# N33_1_0.net
KiCad netlist of a schematic drawn in EAGLE
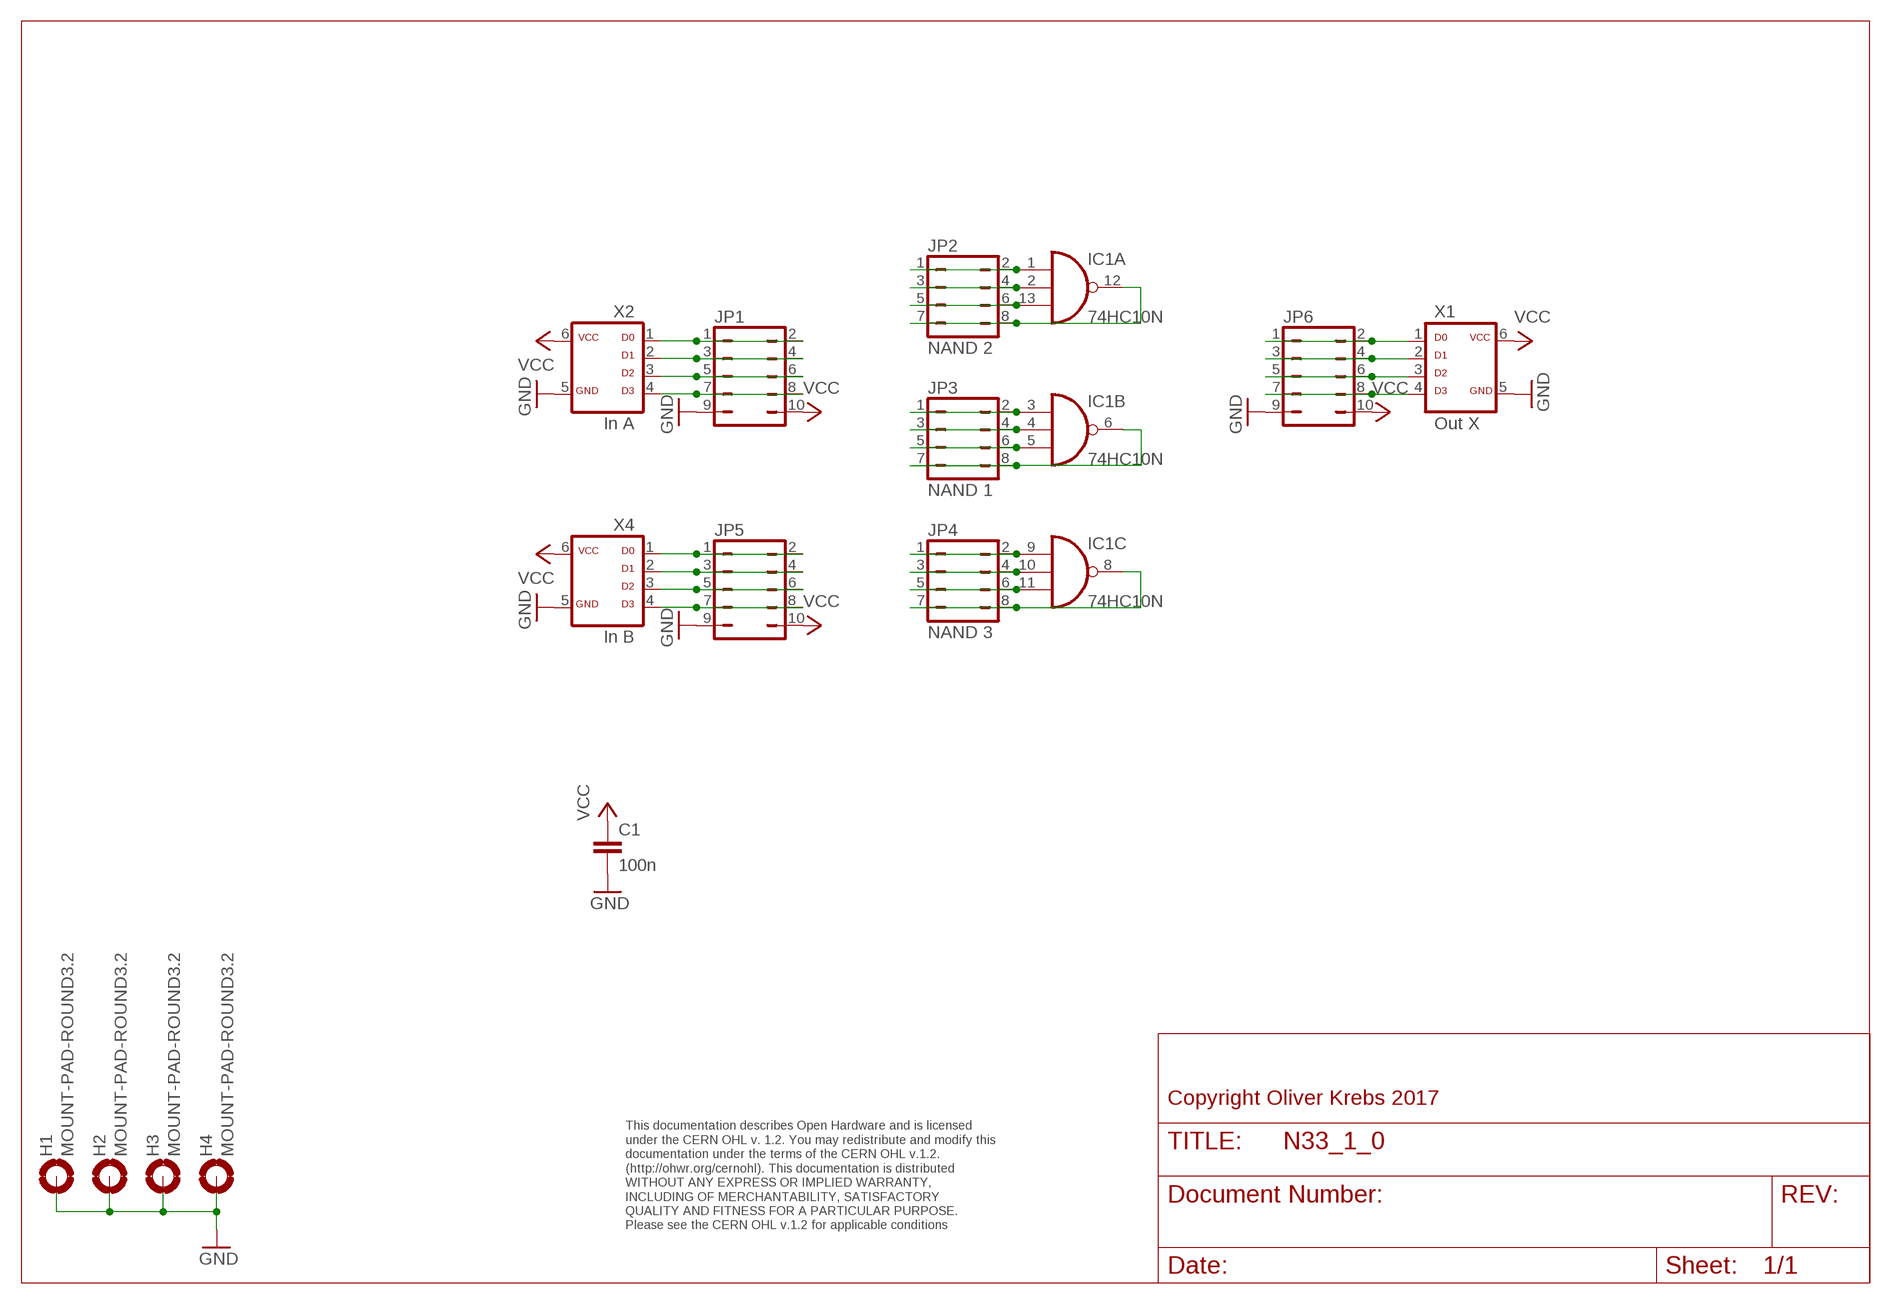
[diagram p0: schematic, sheet 1]

(export (version "E")
  (design (tool "Eeschema 10.0.6"))
  (components
    (comp (ref "C1")
      (value "100n")
      (footprint "eagle-import:C050-025X075")
      (libsource (lib "eagle-import") (part "C-EU050-025X075"))
    )
    (comp (ref "H1")
      (value "MOUNT-PAD-ROUND3.2")
      (footprint "eagle-import:3,2-PAD")
      (libsource (lib "eagle-import") (part "MOUNT-PAD-ROUND3.2"))
    )
    (comp (ref "H2")
      (value "MOUNT-PAD-ROUND3.2")
      (footprint "eagle-import:3,2-PAD")
      (libsource (lib "eagle-import") (part "MOUNT-PAD-ROUND3.2"))
    )
    (comp (ref "H3")
      (value "MOUNT-PAD-ROUND3.2")
      (footprint "eagle-import:3,2-PAD")
      (libsource (lib "eagle-import") (part "MOUNT-PAD-ROUND3.2"))
    )
    (comp (ref "H4")
      (value "MOUNT-PAD-ROUND3.2")
      (footprint "eagle-import:3,2-PAD")
      (libsource (lib "eagle-import") (part "MOUNT-PAD-ROUND3.2"))
    )
    (comp (ref "IC1")
      (value "74HC10N")
      (footprint "eagle-import:DIL14")
      (libsource (lib "eagle-import") (part "7410NHC"))
    )
    (comp (ref "JP1")
      (value "JP5Q")
      (footprint "eagle-import:JP5Q")
      (libsource (lib "eagle-import") (part "JP5Q"))
    )
    (comp (ref "JP2")
      (value "NAND 2")
      (footprint "eagle-import:JP4Q")
      (libsource (lib "eagle-import") (part "JP4Q"))
    )
    (comp (ref "JP3")
      (value "NAND 1")
      (footprint "eagle-import:JP4Q")
      (libsource (lib "eagle-import") (part "JP4Q"))
    )
    (comp (ref "JP4")
      (value "NAND 3")
      (footprint "eagle-import:JP4Q")
      (libsource (lib "eagle-import") (part "JP4Q"))
    )
    (comp (ref "JP5")
      (value "JP5Q")
      (footprint "eagle-import:JP5Q")
      (libsource (lib "eagle-import") (part "JP5Q"))
    )
    (comp (ref "JP6")
      (value "JP5Q")
      (footprint "eagle-import:JP5Q")
      (libsource (lib "eagle-import") (part "JP5Q"))
    )
    (comp (ref "X1")
      (value "Out X")
      (footprint "eagle-import:ML-6")
      (libsource (lib "eagle-import") (part "ML6D"))
    )
    (comp (ref "X2")
      (value "In A")
      (footprint "eagle-import:ML-6")
      (libsource (lib "eagle-import") (part "ML6D"))
    )
    (comp (ref "X4")
      (value "In B")
      (footprint "eagle-import:ML-6")
      (libsource (lib "eagle-import") (part "ML6D"))
    )
  )
  (nets
    (net (code "1") (name "GND") (class "Default")
      (node (ref "C1") (pin "2") (pinfunction "2_2") (pintype "passive"))
      (node (ref "H1") (pin "B3,2") (pinfunction "MOUNT_B3,2") (pintype "passive"))
      (node (ref "H2") (pin "B3,2") (pinfunction "MOUNT_B3,2") (pintype "passive"))
      (node (ref "H3") (pin "B3,2") (pinfunction "MOUNT_B3,2") (pintype "passive"))
      (node (ref "H4") (pin "B3,2") (pinfunction "MOUNT_B3,2") (pintype "passive"))
      (node (ref "JP1") (pin "9") (pinfunction "9_9") (pintype "passive"))
      (node (ref "JP5") (pin "9") (pinfunction "9_9") (pintype "passive"))
      (node (ref "JP6") (pin "9") (pinfunction "9_9") (pintype "passive"))
      (node (ref "X1") (pin "5") (pinfunction "5_5") (pintype "passive"))
      (node (ref "X2") (pin "5") (pinfunction "5_5") (pintype "passive"))
      (node (ref "X4") (pin "5") (pinfunction "5_5") (pintype "passive"))
    )
    (net (code "2") (name "Net-(IC1A-I0)") (class "Default")
      (node (ref "IC1") (pin "1") (pinfunction "I0_1") (pintype "input"))
      (node (ref "JP2") (pin "1") (pinfunction "1_1") (pintype "passive"))
      (node (ref "JP2") (pin "2") (pinfunction "2_2") (pintype "passive"))
    )
    (net (code "3") (name "Net-(IC1A-I1)") (class "Default")
      (node (ref "IC1") (pin "2") (pinfunction "I1_2") (pintype "input"))
      (node (ref "JP2") (pin "3") (pinfunction "3_3") (pintype "passive"))
      (node (ref "JP2") (pin "4") (pinfunction "4_4") (pintype "passive"))
    )
    (net (code "4") (name "Net-(IC1A-I2)") (class "Default")
      (node (ref "IC1") (pin "13") (pinfunction "I2_13") (pintype "input"))
      (node (ref "JP2") (pin "5") (pinfunction "5_5") (pintype "passive"))
      (node (ref "JP2") (pin "6") (pinfunction "6_6") (pintype "passive"))
    )
    (net (code "5") (name "Net-(IC1A-O)") (class "Default")
      (node (ref "IC1") (pin "12") (pinfunction "O_12") (pintype "output"))
      (node (ref "JP2") (pin "7") (pinfunction "7_7") (pintype "passive"))
      (node (ref "JP2") (pin "8") (pinfunction "8_8") (pintype "passive"))
    )
    (net (code "6") (name "Net-(IC1B-I0)") (class "Default")
      (node (ref "IC1") (pin "3") (pinfunction "I0_3") (pintype "input"))
      (node (ref "JP3") (pin "1") (pinfunction "1_1") (pintype "passive"))
      (node (ref "JP3") (pin "2") (pinfunction "2_2") (pintype "passive"))
    )
    (net (code "7") (name "Net-(IC1B-I1)") (class "Default")
      (node (ref "IC1") (pin "4") (pinfunction "I1_4") (pintype "input"))
      (node (ref "JP3") (pin "3") (pinfunction "3_3") (pintype "passive"))
      (node (ref "JP3") (pin "4") (pinfunction "4_4") (pintype "passive"))
    )
    (net (code "8") (name "Net-(IC1B-I2)") (class "Default")
      (node (ref "IC1") (pin "5") (pinfunction "I2_5") (pintype "input"))
      (node (ref "JP3") (pin "5") (pinfunction "5_5") (pintype "passive"))
      (node (ref "JP3") (pin "6") (pinfunction "6_6") (pintype "passive"))
    )
    (net (code "9") (name "Net-(IC1B-O)") (class "Default")
      (node (ref "IC1") (pin "6") (pinfunction "O_6") (pintype "output"))
      (node (ref "JP3") (pin "7") (pinfunction "7_7") (pintype "passive"))
      (node (ref "JP3") (pin "8") (pinfunction "8_8") (pintype "passive"))
    )
    (net (code "10") (name "Net-(IC1C-I0)") (class "Default")
      (node (ref "IC1") (pin "9") (pinfunction "I0_9") (pintype "input"))
      (node (ref "JP4") (pin "1") (pinfunction "1_1") (pintype "passive"))
      (node (ref "JP4") (pin "2") (pinfunction "2_2") (pintype "passive"))
    )
    (net (code "11") (name "Net-(IC1C-I1)") (class "Default")
      (node (ref "IC1") (pin "10") (pinfunction "I1_10") (pintype "input"))
      (node (ref "JP4") (pin "3") (pinfunction "3_3") (pintype "passive"))
      (node (ref "JP4") (pin "4") (pinfunction "4_4") (pintype "passive"))
    )
    (net (code "12") (name "Net-(IC1C-I2)") (class "Default")
      (node (ref "IC1") (pin "11") (pinfunction "I2_11") (pintype "input"))
      (node (ref "JP4") (pin "5") (pinfunction "5_5") (pintype "passive"))
      (node (ref "JP4") (pin "6") (pinfunction "6_6") (pintype "passive"))
    )
    (net (code "13") (name "Net-(IC1C-O)") (class "Default")
      (node (ref "IC1") (pin "8") (pinfunction "O_8") (pintype "output"))
      (node (ref "JP4") (pin "7") (pinfunction "7_7") (pintype "passive"))
      (node (ref "JP4") (pin "8") (pinfunction "8_8") (pintype "passive"))
    )
    (net (code "14") (name "Net-(JP1-Pad1)") (class "Default")
      (node (ref "JP1") (pin "1") (pinfunction "1_1") (pintype "passive"))
      (node (ref "JP1") (pin "2") (pinfunction "2_2") (pintype "passive"))
      (node (ref "X2") (pin "1") (pinfunction "1_1") (pintype "passive"))
    )
    (net (code "15") (name "Net-(JP1-Pad3)") (class "Default")
      (node (ref "JP1") (pin "3") (pinfunction "3_3") (pintype "passive"))
      (node (ref "JP1") (pin "4") (pinfunction "4_4") (pintype "passive"))
      (node (ref "X2") (pin "2") (pinfunction "2_2") (pintype "passive"))
    )
    (net (code "16") (name "Net-(JP1-Pad5)") (class "Default")
      (node (ref "JP1") (pin "5") (pinfunction "5_5") (pintype "passive"))
      (node (ref "JP1") (pin "6") (pinfunction "6_6") (pintype "passive"))
      (node (ref "X2") (pin "3") (pinfunction "3_3") (pintype "passive"))
    )
    (net (code "17") (name "Net-(JP1-Pad7)") (class "Default")
      (node (ref "JP1") (pin "7") (pinfunction "7_7") (pintype "passive"))
      (node (ref "JP1") (pin "8") (pinfunction "8_8") (pintype "passive"))
      (node (ref "X2") (pin "4") (pinfunction "4_4") (pintype "passive"))
    )
    (net (code "18") (name "Net-(JP5-Pad1)") (class "Default")
      (node (ref "JP5") (pin "1") (pinfunction "1_1") (pintype "passive"))
      (node (ref "JP5") (pin "2") (pinfunction "2_2") (pintype "passive"))
      (node (ref "X4") (pin "1") (pinfunction "1_1") (pintype "passive"))
    )
    (net (code "19") (name "Net-(JP5-Pad3)") (class "Default")
      (node (ref "JP5") (pin "3") (pinfunction "3_3") (pintype "passive"))
      (node (ref "JP5") (pin "4") (pinfunction "4_4") (pintype "passive"))
      (node (ref "X4") (pin "2") (pinfunction "2_2") (pintype "passive"))
    )
    (net (code "20") (name "Net-(JP5-Pad5)") (class "Default")
      (node (ref "JP5") (pin "5") (pinfunction "5_5") (pintype "passive"))
      (node (ref "JP5") (pin "6") (pinfunction "6_6") (pintype "passive"))
      (node (ref "X4") (pin "3") (pinfunction "3_3") (pintype "passive"))
    )
    (net (code "21") (name "Net-(JP5-Pad7)") (class "Default")
      (node (ref "JP5") (pin "7") (pinfunction "7_7") (pintype "passive"))
      (node (ref "JP5") (pin "8") (pinfunction "8_8") (pintype "passive"))
      (node (ref "X4") (pin "4") (pinfunction "4_4") (pintype "passive"))
    )
    (net (code "22") (name "Net-(JP6-Pad1)") (class "Default")
      (node (ref "JP6") (pin "1") (pinfunction "1_1") (pintype "passive"))
      (node (ref "JP6") (pin "2") (pinfunction "2_2") (pintype "passive"))
      (node (ref "X1") (pin "1") (pinfunction "1_1") (pintype "passive"))
    )
    (net (code "23") (name "Net-(JP6-Pad3)") (class "Default")
      (node (ref "JP6") (pin "3") (pinfunction "3_3") (pintype "passive"))
      (node (ref "JP6") (pin "4") (pinfunction "4_4") (pintype "passive"))
      (node (ref "X1") (pin "2") (pinfunction "2_2") (pintype "passive"))
    )
    (net (code "24") (name "Net-(JP6-Pad5)") (class "Default")
      (node (ref "JP6") (pin "5") (pinfunction "5_5") (pintype "passive"))
      (node (ref "JP6") (pin "6") (pinfunction "6_6") (pintype "passive"))
      (node (ref "X1") (pin "3") (pinfunction "3_3") (pintype "passive"))
    )
    (net (code "25") (name "Net-(JP6-Pad7)") (class "Default")
      (node (ref "JP6") (pin "7") (pinfunction "7_7") (pintype "passive"))
      (node (ref "JP6") (pin "8") (pinfunction "8_8") (pintype "passive"))
      (node (ref "X1") (pin "4") (pinfunction "4_4") (pintype "passive"))
    )
    (net (code "26") (name "VCC") (class "Default")
      (node (ref "C1") (pin "1") (pinfunction "1_1") (pintype "passive"))
      (node (ref "JP1") (pin "10") (pinfunction "10_10") (pintype "passive"))
      (node (ref "JP5") (pin "10") (pinfunction "10_10") (pintype "passive"))
      (node (ref "JP6") (pin "10") (pinfunction "10_10") (pintype "passive"))
      (node (ref "X1") (pin "6") (pinfunction "6_6") (pintype "passive"))
      (node (ref "X2") (pin "6") (pinfunction "6_6") (pintype "passive"))
      (node (ref "X4") (pin "6") (pinfunction "6_6") (pintype "passive"))
    )
  )
)
